# 09_-_PERIPHERALS_D.net
KiCad netlist of a schematic drawn in Altium Designer
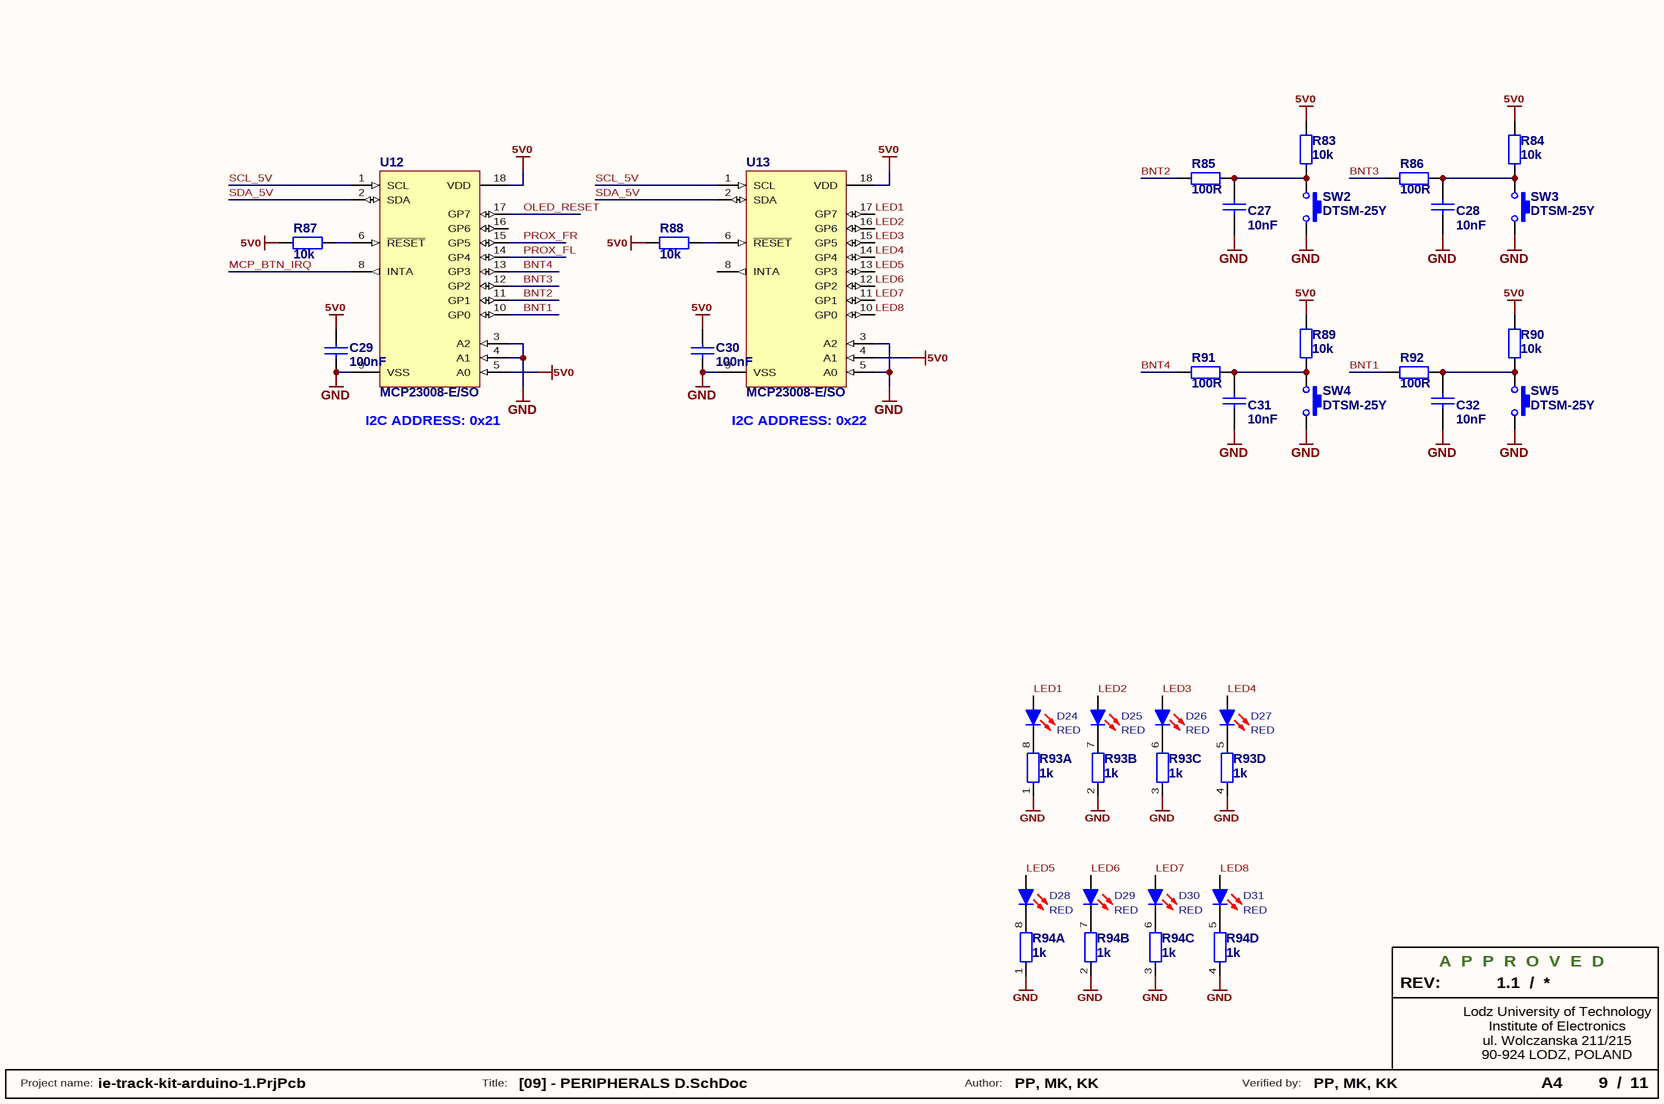
[diagram p0: [09] - PERIPHERALS D.SchDoc]

(export (version "E")
  (design (tool "Eeschema 10.0.6"))
  (components
    (comp (ref "C27")
      (value "10nF")
      (footprint "C0805")
      (description "Capacitor")
      (libsource (lib "capacitors") (part "Cap"))
    )
    (comp (ref "C28")
      (value "10nF")
      (footprint "C0805")
      (description "Capacitor")
      (libsource (lib "capacitors") (part "Cap"))
    )
    (comp (ref "C29")
      (value "100nF")
      (footprint "C0805")
      (description "Capacitor")
      (libsource (lib "") (part "Cap_1"))
    )
    (comp (ref "C30")
      (value "100nF")
      (footprint "C0805")
      (description "Capacitor")
      (libsource (lib "") (part "Cap_1"))
    )
    (comp (ref "C31")
      (value "10nF")
      (footprint "C0805")
      (description "Capacitor")
      (libsource (lib "capacitors") (part "Cap"))
    )
    (comp (ref "C32")
      (value "10nF")
      (footprint "C0805")
      (description "Capacitor")
      (libsource (lib "capacitors") (part "Cap"))
    )
    (comp (ref "D24")
      (value "RED")
      (footprint "LED0805R")
      (description "RED LED")
      (libsource (lib "leds") (part "LED_RED"))
    )
    (comp (ref "D25")
      (value "RED")
      (footprint "LED0805R")
      (description "RED LED")
      (libsource (lib "leds") (part "LED_RED"))
    )
    (comp (ref "D26")
      (value "RED")
      (footprint "LED0805R")
      (description "RED LED")
      (libsource (lib "leds") (part "LED_RED"))
    )
    (comp (ref "D27")
      (value "RED")
      (footprint "LED0805R")
      (description "RED LED")
      (libsource (lib "leds") (part "LED_RED"))
    )
    (comp (ref "D28")
      (value "RED")
      (footprint "LED0805R")
      (description "RED LED")
      (libsource (lib "leds") (part "LED_RED"))
    )
    (comp (ref "D29")
      (value "RED")
      (footprint "LED0805R")
      (description "RED LED")
      (libsource (lib "leds") (part "LED_RED"))
    )
    (comp (ref "D30")
      (value "RED")
      (footprint "LED0805R")
      (description "RED LED")
      (libsource (lib "leds") (part "LED_RED"))
    )
    (comp (ref "D31")
      (value "RED")
      (footprint "LED0805R")
      (description "RED LED")
      (libsource (lib "leds") (part "LED_RED"))
    )
    (comp (ref "R83")
      (value "10k")
      (footprint "R0805")
      (description "Resistor")
      (libsource (lib "") (part "Res_2"))
    )
    (comp (ref "R84")
      (value "10k")
      (footprint "R0805")
      (description "Resistor")
      (libsource (lib "") (part "Res_2"))
    )
    (comp (ref "R85")
      (value "100R")
      (footprint "R0805")
      (description "Resistor")
      (libsource (lib "") (part "Res_1"))
    )
    (comp (ref "R86")
      (value "100R")
      (footprint "R0805")
      (description "Resistor")
      (libsource (lib "") (part "Res_1"))
    )
    (comp (ref "R87")
      (value "10k")
      (footprint "R0805")
      (description "Resistor")
      (libsource (lib "resistors") (part "Res"))
    )
    (comp (ref "R88")
      (value "10k")
      (footprint "R0805")
      (description "Resistor")
      (libsource (lib "resistors") (part "Res"))
    )
    (comp (ref "R89")
      (value "10k")
      (footprint "R0805")
      (description "Resistor")
      (libsource (lib "") (part "Res_2"))
    )
    (comp (ref "R90")
      (value "10k")
      (footprint "R0805")
      (description "Resistor")
      (libsource (lib "") (part "Res_2"))
    )
    (comp (ref "R91")
      (value "100R")
      (footprint "R0805")
      (description "Resistor")
      (libsource (lib "") (part "Res_1"))
    )
    (comp (ref "R92")
      (value "100R")
      (footprint "R0805")
      (description "Resistor")
      (libsource (lib "") (part "Res_1"))
    )
    (comp (ref "R93")
      (value "1k")
      (footprint "RPack_0603x4_1206")
      (description "Isolated Resistor Network - Parts")
      (fields (field (name "PUBLISHER") "Altium Limited"))
      (libsource (lib "resistors") (part "Res Pack4_1"))
    )
    (comp (ref "R94")
      (value "1k")
      (footprint "RPack_0603x4_1206")
      (description "Isolated Resistor Network - Parts")
      (fields (field (name "PUBLISHER") "Altium Limited"))
      (libsource (lib "resistors") (part "Res Pack4_1"))
    )
    (comp (ref "SW2")
      (value "DTSM-25Y")
      (footprint "DTSM-25Y")
      (description "DIPTRONICS Yellow 12x12mm SMD Tactile SPST-NO Switch")
      (libsource (lib "microswitches") (part "DTSM-25Y"))
    )
    (comp (ref "SW3")
      (value "DTSM-25Y")
      (footprint "DTSM-25Y")
      (description "DIPTRONICS Yellow 12x12mm SMD Tactile SPST-NO Switch")
      (libsource (lib "microswitches") (part "DTSM-25Y"))
    )
    (comp (ref "SW4")
      (value "DTSM-25Y")
      (footprint "DTSM-25Y")
      (description "DIPTRONICS Yellow 12x12mm SMD Tactile SPST-NO Switch")
      (libsource (lib "microswitches") (part "DTSM-25Y"))
    )
    (comp (ref "SW5")
      (value "DTSM-25Y")
      (footprint "DTSM-25Y")
      (description "DIPTRONICS Yellow 12x12mm SMD Tactile SPST-NO Switch")
      (libsource (lib "microswitches") (part "DTSM-25Y"))
    )
    (comp (ref "U12")
      (value "MCP23008-E/SO")
      (footprint "SO18W")
      (description "8-Bit I/O Expander with Serial Interface I2C, 18-Pin SOIC Package")
      (libsource (lib "io_expanders") (part "MCP23008-E/SO"))
    )
    (comp (ref "U13")
      (value "MCP23008-E/SO")
      (footprint "SO18W")
      (description "8-Bit I/O Expander with Serial Interface I2C, 18-Pin SOIC Package")
      (libsource (lib "io_expanders") (part "MCP23008-E/SO"))
    )
  )
  (nets
    (net (code "1") (name "/BNT1") (class "Default")
      (node (ref "R92") (pin "1") (pinfunction "1_1") (pintype "passive"))
      (node (ref "U12") (pin "10") (pinfunction "GP0_10") (pintype "bidirectional"))
    )
    (net (code "2") (name "/BNT2") (class "Default")
      (node (ref "R85") (pin "1") (pinfunction "1_1") (pintype "passive"))
      (node (ref "U12") (pin "11") (pinfunction "GP1_11") (pintype "bidirectional"))
    )
    (net (code "3") (name "/BNT3") (class "Default")
      (node (ref "R86") (pin "1") (pinfunction "1_1") (pintype "passive"))
      (node (ref "U12") (pin "12") (pinfunction "GP2_12") (pintype "bidirectional"))
    )
    (net (code "4") (name "/BNT4") (class "Default")
      (node (ref "R91") (pin "1") (pinfunction "1_1") (pintype "passive"))
      (node (ref "U12") (pin "13") (pinfunction "GP3_13") (pintype "bidirectional"))
    )
    (net (code "5") (name "/LED1") (class "Default")
      (node (ref "D24") (pin "1") (pinfunction "A_1") (pintype "passive"))
      (node (ref "U13") (pin "17") (pinfunction "GP7_17") (pintype "bidirectional"))
    )
    (net (code "6") (name "/LED2") (class "Default")
      (node (ref "D25") (pin "1") (pinfunction "A_1") (pintype "passive"))
      (node (ref "U13") (pin "16") (pinfunction "GP6_16") (pintype "bidirectional"))
    )
    (net (code "7") (name "/LED3") (class "Default")
      (node (ref "D26") (pin "1") (pinfunction "A_1") (pintype "passive"))
      (node (ref "U13") (pin "15") (pinfunction "GP5_15") (pintype "bidirectional"))
    )
    (net (code "8") (name "/LED4") (class "Default")
      (node (ref "D27") (pin "1") (pinfunction "A_1") (pintype "passive"))
      (node (ref "U13") (pin "14") (pinfunction "GP4_14") (pintype "bidirectional"))
    )
    (net (code "9") (name "/LED5") (class "Default")
      (node (ref "D28") (pin "1") (pinfunction "A_1") (pintype "passive"))
      (node (ref "U13") (pin "13") (pinfunction "GP3_13") (pintype "bidirectional"))
    )
    (net (code "10") (name "/LED6") (class "Default")
      (node (ref "D29") (pin "1") (pinfunction "A_1") (pintype "passive"))
      (node (ref "U13") (pin "12") (pinfunction "GP2_12") (pintype "bidirectional"))
    )
    (net (code "11") (name "/LED7") (class "Default")
      (node (ref "D30") (pin "1") (pinfunction "A_1") (pintype "passive"))
      (node (ref "U13") (pin "11") (pinfunction "GP1_11") (pintype "bidirectional"))
    )
    (net (code "12") (name "/LED8") (class "Default")
      (node (ref "D31") (pin "1") (pinfunction "A_1") (pintype "passive"))
      (node (ref "U13") (pin "10") (pinfunction "GP0_10") (pintype "bidirectional"))
    )
    (net (code "13") (name "/MCP_BTN_IRQ") (class "Default")
      (node (ref "U12") (pin "8") (pinfunction "INTA_8") (pintype "output"))
    )
    (net (code "14") (name "/OLED_RESET") (class "Default")
      (node (ref "U12") (pin "17") (pinfunction "GP7_17") (pintype "bidirectional"))
    )
    (net (code "15") (name "/PROX_FL") (class "Default")
      (node (ref "U12") (pin "14") (pinfunction "GP4_14") (pintype "bidirectional"))
    )
    (net (code "16") (name "/PROX_FR") (class "Default")
      (node (ref "U12") (pin "15") (pinfunction "GP5_15") (pintype "bidirectional"))
    )
    (net (code "17") (name "/SCL_5V") (class "Default")
      (node (ref "U12") (pin "1") (pinfunction "SCL_1") (pintype "input"))
      (node (ref "U13") (pin "1") (pinfunction "SCL_1") (pintype "input"))
    )
    (net (code "18") (name "/SDA_5V") (class "Default")
      (node (ref "U12") (pin "2") (pinfunction "SDA_2") (pintype "bidirectional"))
      (node (ref "U13") (pin "2") (pinfunction "SDA_2") (pintype "bidirectional"))
    )
    (net (code "19") (name "5V0") (class "Default")
      (node (ref "C29") (pin "2") (pinfunction "2_2") (pintype "passive"))
      (node (ref "C30") (pin "2") (pinfunction "2_2") (pintype "passive"))
      (node (ref "R83") (pin "2") (pinfunction "2_2") (pintype "passive"))
      (node (ref "R84") (pin "2") (pinfunction "2_2") (pintype "passive"))
      (node (ref "R87") (pin "1") (pinfunction "1_1") (pintype "passive"))
      (node (ref "R88") (pin "1") (pinfunction "1_1") (pintype "passive"))
      (node (ref "R89") (pin "2") (pinfunction "2_2") (pintype "passive"))
      (node (ref "R90") (pin "2") (pinfunction "2_2") (pintype "passive"))
      (node (ref "U12") (pin "18") (pinfunction "VDD_18") (pintype "power_in"))
      (node (ref "U12") (pin "5") (pinfunction "A0_5") (pintype "input"))
      (node (ref "U13") (pin "18") (pinfunction "VDD_18") (pintype "power_in"))
      (node (ref "U13") (pin "4") (pinfunction "A1_4") (pintype "input"))
    )
    (net (code "20") (name "GND") (class "Default")
      (node (ref "C27") (pin "1") (pinfunction "1_1") (pintype "passive"))
      (node (ref "C28") (pin "1") (pinfunction "1_1") (pintype "passive"))
      (node (ref "C29") (pin "1") (pinfunction "1_1") (pintype "passive"))
      (node (ref "C30") (pin "1") (pinfunction "1_1") (pintype "passive"))
      (node (ref "C31") (pin "1") (pinfunction "1_1") (pintype "passive"))
      (node (ref "C32") (pin "1") (pinfunction "1_1") (pintype "passive"))
      (node (ref "R93") (pin "1") (pinfunction "1_1") (pintype "passive"))
      (node (ref "R93") (pin "2") (pinfunction "2_2") (pintype "passive"))
      (node (ref "R93") (pin "3") (pinfunction "3_3") (pintype "passive"))
      (node (ref "R93") (pin "4") (pinfunction "4_4") (pintype "passive"))
      (node (ref "R94") (pin "1") (pinfunction "1_1") (pintype "passive"))
      (node (ref "R94") (pin "2") (pinfunction "2_2") (pintype "passive"))
      (node (ref "R94") (pin "3") (pinfunction "3_3") (pintype "passive"))
      (node (ref "R94") (pin "4") (pinfunction "4_4") (pintype "passive"))
      (node (ref "SW2") (pin "2") (pinfunction "2_2") (pintype "passive"))
      (node (ref "SW3") (pin "2") (pinfunction "2_2") (pintype "passive"))
      (node (ref "SW4") (pin "2") (pinfunction "2_2") (pintype "passive"))
      (node (ref "SW5") (pin "2") (pinfunction "2_2") (pintype "passive"))
      (node (ref "U12") (pin "3") (pinfunction "A2_3") (pintype "input"))
      (node (ref "U12") (pin "4") (pinfunction "A1_4") (pintype "input"))
      (node (ref "U12") (pin "9") (pinfunction "VSS_9") (pintype "power_in"))
      (node (ref "U13") (pin "3") (pinfunction "A2_3") (pintype "input"))
      (node (ref "U13") (pin "5") (pinfunction "A0_5") (pintype "input"))
      (node (ref "U13") (pin "9") (pinfunction "VSS_9") (pintype "power_in"))
    )
    (net (code "21") (name "Net-(C27-Pad2)") (class "Default")
      (node (ref "C27") (pin "2") (pinfunction "2_2") (pintype "passive"))
      (node (ref "R83") (pin "1") (pinfunction "1_1") (pintype "passive"))
      (node (ref "R85") (pin "2") (pinfunction "2_2") (pintype "passive"))
      (node (ref "SW2") (pin "1") (pinfunction "1_1") (pintype "passive"))
    )
    (net (code "22") (name "Net-(C28-Pad2)") (class "Default")
      (node (ref "C28") (pin "2") (pinfunction "2_2") (pintype "passive"))
      (node (ref "R84") (pin "1") (pinfunction "1_1") (pintype "passive"))
      (node (ref "R86") (pin "2") (pinfunction "2_2") (pintype "passive"))
      (node (ref "SW3") (pin "1") (pinfunction "1_1") (pintype "passive"))
    )
    (net (code "23") (name "Net-(C31-Pad2)") (class "Default")
      (node (ref "C31") (pin "2") (pinfunction "2_2") (pintype "passive"))
      (node (ref "R89") (pin "1") (pinfunction "1_1") (pintype "passive"))
      (node (ref "R91") (pin "2") (pinfunction "2_2") (pintype "passive"))
      (node (ref "SW4") (pin "1") (pinfunction "1_1") (pintype "passive"))
    )
    (net (code "24") (name "Net-(C32-Pad2)") (class "Default")
      (node (ref "C32") (pin "2") (pinfunction "2_2") (pintype "passive"))
      (node (ref "R90") (pin "1") (pinfunction "1_1") (pintype "passive"))
      (node (ref "R92") (pin "2") (pinfunction "2_2") (pintype "passive"))
      (node (ref "SW5") (pin "1") (pinfunction "1_1") (pintype "passive"))
    )
    (net (code "25") (name "Net-(D24-K)") (class "Default")
      (node (ref "D24") (pin "2") (pinfunction "K_2") (pintype "passive"))
      (node (ref "R93") (pin "8") (pinfunction "8_8") (pintype "passive"))
    )
    (net (code "26") (name "Net-(D25-K)") (class "Default")
      (node (ref "D25") (pin "2") (pinfunction "K_2") (pintype "passive"))
      (node (ref "R93") (pin "7") (pinfunction "7_7") (pintype "passive"))
    )
    (net (code "27") (name "Net-(D26-K)") (class "Default")
      (node (ref "D26") (pin "2") (pinfunction "K_2") (pintype "passive"))
      (node (ref "R93") (pin "6") (pinfunction "6_6") (pintype "passive"))
    )
    (net (code "28") (name "Net-(D27-K)") (class "Default")
      (node (ref "D27") (pin "2") (pinfunction "K_2") (pintype "passive"))
      (node (ref "R93") (pin "5") (pinfunction "5_5") (pintype "passive"))
    )
    (net (code "29") (name "Net-(D28-K)") (class "Default")
      (node (ref "D28") (pin "2") (pinfunction "K_2") (pintype "passive"))
      (node (ref "R94") (pin "8") (pinfunction "8_8") (pintype "passive"))
    )
    (net (code "30") (name "Net-(D29-K)") (class "Default")
      (node (ref "D29") (pin "2") (pinfunction "K_2") (pintype "passive"))
      (node (ref "R94") (pin "7") (pinfunction "7_7") (pintype "passive"))
    )
    (net (code "31") (name "Net-(D30-K)") (class "Default")
      (node (ref "D30") (pin "2") (pinfunction "K_2") (pintype "passive"))
      (node (ref "R94") (pin "6") (pinfunction "6_6") (pintype "passive"))
    )
    (net (code "32") (name "Net-(D31-K)") (class "Default")
      (node (ref "D31") (pin "2") (pinfunction "K_2") (pintype "passive"))
      (node (ref "R94") (pin "5") (pinfunction "5_5") (pintype "passive"))
    )
    (net (code "33") (name "Net-(U12-~{RESET})") (class "Default")
      (node (ref "R87") (pin "2") (pinfunction "2_2") (pintype "passive"))
      (node (ref "U12") (pin "6") (pinfunction "~{RESET}_6") (pintype "input"))
    )
    (net (code "34") (name "Net-(U13-~{RESET})") (class "Default")
      (node (ref "R88") (pin "2") (pinfunction "2_2") (pintype "passive"))
      (node (ref "U13") (pin "6") (pinfunction "~{RESET}_6") (pintype "input"))
    )
    (net (code "35") (name "unconnected-(U12-GP6-Pad16)") (class "Default")
      (node (ref "U12") (pin "16") (pinfunction "GP6_16") (pintype "bidirectional"))
    )
    (net (code "36") (name "unconnected-(U13-INTA-Pad8)") (class "Default")
      (node (ref "U13") (pin "8") (pinfunction "INTA_8") (pintype "output"))
    )
  )
)
